# FXAS21002_gyro.net
KiCad netlist of a schematic drawn in EAGLE
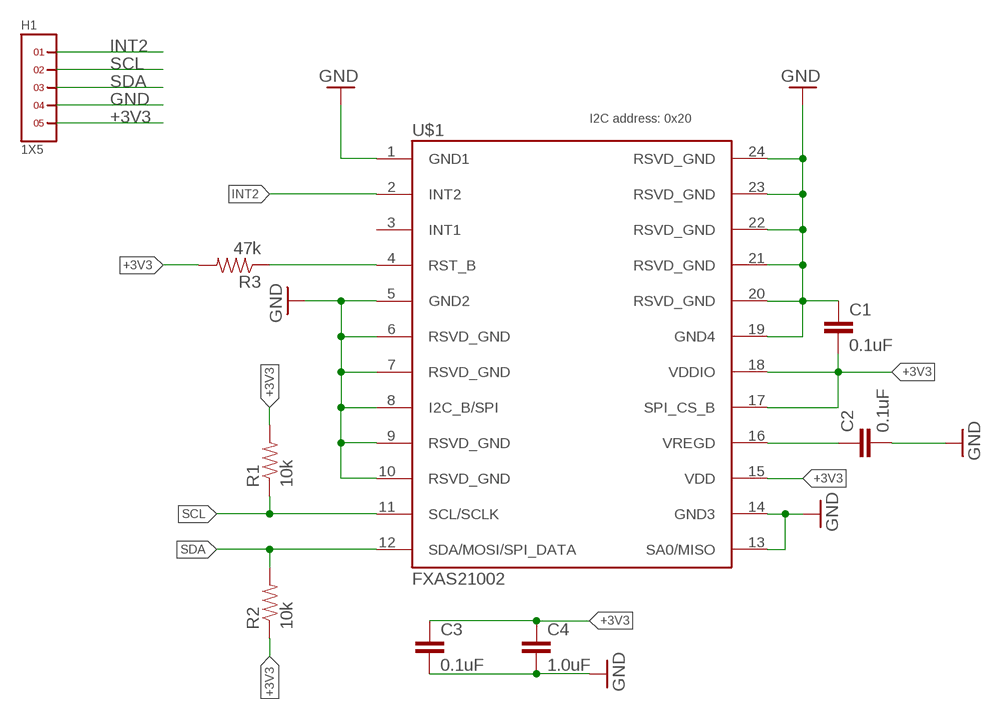
[diagram p0: schematic, sheet 1]

(export (version "E")
  (design (tool "Eeschema 10.0.6"))
  (components
    (comp (ref "C1")
      (value "0.1uF")
      (footprint "eagle-import:0805")
      (libsource (lib "eagle-import") (part "CAP0805"))
    )
    (comp (ref "C2")
      (value "0.1uF")
      (footprint "eagle-import:0805")
      (libsource (lib "eagle-import") (part "CAP0805"))
    )
    (comp (ref "C3")
      (value "0.1uF")
      (footprint "eagle-import:0805")
      (libsource (lib "eagle-import") (part "CAP0805"))
    )
    (comp (ref "C4")
      (value "1.0uF")
      (footprint "eagle-import:0805")
      (libsource (lib "eagle-import") (part "CAP0805"))
    )
    (comp (ref "H1")
      (value "1X5")
      (footprint "eagle-import:1X5")
      (libsource (lib "eagle-import") (part "1X5"))
    )
    (comp (ref "R1")
      (value "10k")
      (footprint "eagle-import:0805")
      (libsource (lib "eagle-import") (part "RESISTOR0805-RES"))
    )
    (comp (ref "R2")
      (value "10k")
      (footprint "eagle-import:0805")
      (libsource (lib "eagle-import") (part "RESISTOR0805-RES"))
    )
    (comp (ref "R3")
      (value "47k")
      (footprint "eagle-import:0805")
      (libsource (lib "eagle-import") (part "RESISTOR0805-RES"))
    )
    (comp (ref "U$1")
      (value "FXAS21002")
      (footprint "eagle-import:24QFN")
      (libsource (lib "eagle-import") (part "FXAS21002"))
    )
  )
  (nets
    (net (code "1") (name "+3V3") (class "Default")
      (node (ref "C1") (pin "2") (pinfunction "2_2") (pintype "passive"))
      (node (ref "C3") (pin "1") (pinfunction "1_1") (pintype "passive"))
      (node (ref "C4") (pin "1") (pinfunction "1_1") (pintype "passive"))
      (node (ref "H1") (pin "5") (pinfunction "5_5") (pintype "bidirectional"))
      (node (ref "R1") (pin "2") (pinfunction "2_2") (pintype "passive"))
      (node (ref "R2") (pin "1") (pinfunction "1_1") (pintype "passive"))
      (node (ref "R3") (pin "2") (pinfunction "2_2") (pintype "passive"))
      (node (ref "U$1") (pin "15") (pinfunction "VDD_15") (pintype "bidirectional"))
      (node (ref "U$1") (pin "17") (pinfunction "SPI_CS_B_17") (pintype "bidirectional"))
      (node (ref "U$1") (pin "18") (pinfunction "VDDIO_18") (pintype "bidirectional"))
    )
    (net (code "2") (name "GND") (class "Default")
      (node (ref "C1") (pin "1") (pinfunction "1_1") (pintype "passive"))
      (node (ref "C2") (pin "2") (pinfunction "2_2") (pintype "passive"))
      (node (ref "C3") (pin "2") (pinfunction "2_2") (pintype "passive"))
      (node (ref "C4") (pin "2") (pinfunction "2_2") (pintype "passive"))
      (node (ref "H1") (pin "4") (pinfunction "4_4") (pintype "bidirectional"))
      (node (ref "U$1") (pin "1") (pinfunction "GND1_1") (pintype "bidirectional"))
      (node (ref "U$1") (pin "10") (pinfunction "RSVD_GND_10") (pintype "bidirectional"))
      (node (ref "U$1") (pin "13") (pinfunction "SA0/MISO_13") (pintype "bidirectional"))
      (node (ref "U$1") (pin "14") (pinfunction "GND3_14") (pintype "bidirectional"))
      (node (ref "U$1") (pin "19") (pinfunction "GND4_19") (pintype "bidirectional"))
      (node (ref "U$1") (pin "20") (pinfunction "RSVD_GND_20") (pintype "bidirectional"))
      (node (ref "U$1") (pin "21") (pinfunction "RSVD_GND_21") (pintype "bidirectional"))
      (node (ref "U$1") (pin "22") (pinfunction "RSVD_GND_22") (pintype "bidirectional"))
      (node (ref "U$1") (pin "23") (pinfunction "RSVD_GND_23") (pintype "bidirectional"))
      (node (ref "U$1") (pin "24") (pinfunction "RSVD_GND_24") (pintype "bidirectional"))
      (node (ref "U$1") (pin "5") (pinfunction "GND2_5") (pintype "bidirectional"))
      (node (ref "U$1") (pin "6") (pinfunction "RSVD_GND_6") (pintype "bidirectional"))
      (node (ref "U$1") (pin "7") (pinfunction "RSVD_GND_7") (pintype "bidirectional"))
      (node (ref "U$1") (pin "8") (pinfunction "I2C_B/SPI_8") (pintype "bidirectional"))
      (node (ref "U$1") (pin "9") (pinfunction "RSVD_GND_9") (pintype "bidirectional"))
    )
    (net (code "3") (name "INT2") (class "Default")
      (node (ref "H1") (pin "1") (pinfunction "1_1") (pintype "bidirectional"))
      (node (ref "U$1") (pin "2") (pinfunction "INT2_2") (pintype "bidirectional"))
    )
    (net (code "4") (name "Net-(U$1-RST_B)") (class "Default")
      (node (ref "R3") (pin "1") (pinfunction "1_1") (pintype "passive"))
      (node (ref "U$1") (pin "4") (pinfunction "RST_B_4") (pintype "bidirectional"))
    )
    (net (code "5") (name "Net-(U$1-VREGD)") (class "Default")
      (node (ref "C2") (pin "1") (pinfunction "1_1") (pintype "passive"))
      (node (ref "U$1") (pin "16") (pinfunction "VREGD_16") (pintype "bidirectional"))
    )
    (net (code "6") (name "SCL") (class "Default")
      (node (ref "H1") (pin "2") (pinfunction "2_2") (pintype "bidirectional"))
      (node (ref "R1") (pin "1") (pinfunction "1_1") (pintype "passive"))
      (node (ref "U$1") (pin "11") (pinfunction "SCL/SCLK_11") (pintype "bidirectional"))
    )
    (net (code "7") (name "SDA") (class "Default")
      (node (ref "H1") (pin "3") (pinfunction "3_3") (pintype "bidirectional"))
      (node (ref "R2") (pin "2") (pinfunction "2_2") (pintype "passive"))
      (node (ref "U$1") (pin "12") (pinfunction "SDA/MOSI/SPI_DATA_12") (pintype "bidirectional"))
    )
    (net (code "8") (name "unconnected-(U$1-INT1-Pad3)") (class "Default")
      (node (ref "U$1") (pin "3") (pinfunction "INT1_3") (pintype "bidirectional"))
    )
  )
)
